# SMD_Hardware_V0_1.net
KiCad netlist of a schematic drawn in EAGLE
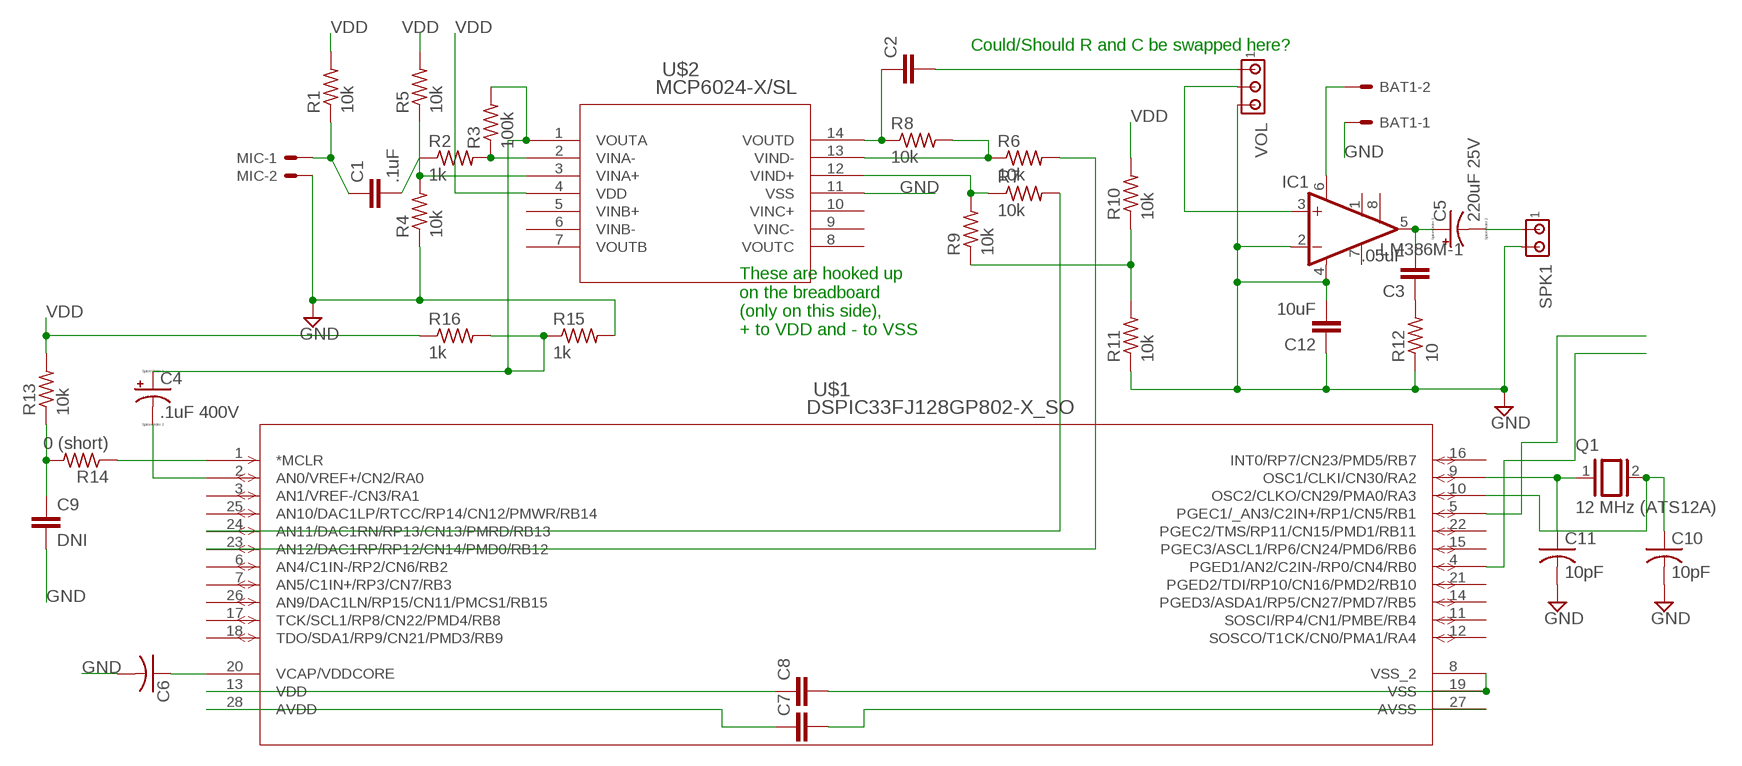
[diagram p0: schematic, sheet 1]

(export (version "E")
  (design (tool "Eeschema 10.0.6"))
  (components
    (comp (ref "BAT1")
      (value "22-23-2021")
      (footprint "eagle-import:22-23-2021")
      (fields (field (name "MF") "MOLEX"))
      (libsource (lib "eagle-import") (part "22-23-2021"))
    )
    (comp (ref "C1")
      (value ".1uF")
      (footprint "eagle-import:C0603")
      (libsource (lib "eagle-import") (part "C-EUC0603"))
    )
    (comp (ref "C2")
      (value "C-EUC0603")
      (footprint "eagle-import:C0603")
      (libsource (lib "eagle-import") (part "C-EUC0603"))
    )
    (comp (ref "C3")
      (value ".05uF")
      (footprint "eagle-import:C0603")
      (libsource (lib "eagle-import") (part "C-EUC0603"))
    )
    (comp (ref "C4")
      (value ".1uF 400V")
      (footprint "eagle-import:140CLH-0810")
      (libsource (lib "eagle-import") (part "CPOL-US140CLH-0810"))
    )
    (comp (ref "C5")
      (value "220uF 25V")
      (footprint "eagle-import:140CLH-0810")
      (libsource (lib "eagle-import") (part "CPOL-US140CLH-0810"))
    )
    (comp (ref "C6")
      (value "C-USC0805")
      (footprint "eagle-import:C0805")
      (libsource (lib "eagle-import") (part "C-USC0805"))
    )
    (comp (ref "C7")
      (value "C-EUC0805")
      (footprint "eagle-import:C0805")
      (libsource (lib "eagle-import") (part "C-EUC0805"))
    )
    (comp (ref "C8")
      (value "C-EUC0805")
      (footprint "eagle-import:C0805")
      (libsource (lib "eagle-import") (part "C-EUC0805"))
    )
    (comp (ref "C9")
      (value "DNI")
      (footprint "eagle-import:C0805")
      (libsource (lib "eagle-import") (part "C-EUC0805"))
    )
    (comp (ref "C10")
      (value "10pF")
      (footprint "eagle-import:C025-024X044")
      (libsource (lib "eagle-import") (part "C-US025-024X044"))
    )
    (comp (ref "C11")
      (value "10pF")
      (footprint "eagle-import:C025-024X044")
      (libsource (lib "eagle-import") (part "C-US025-024X044"))
    )
    (comp (ref "C12")
      (value "10uF")
      (footprint "eagle-import:C0603")
      (libsource (lib "eagle-import") (part "C-EUC0603"))
    )
    (comp (ref "IC1")
      (value "LM386M-1")
      (footprint "eagle-import:SO08")
      (libsource (lib "eagle-import") (part "LM386?-M1"))
    )
    (comp (ref "MIC")
      (value "22-23-2021")
      (footprint "eagle-import:22-23-2021")
      (fields (field (name "MF") "MOLEX"))
      (libsource (lib "eagle-import") (part "22-23-2021"))
    )
    (comp (ref "Q1")
      (value "12 MHz (ATS12A)")
      (footprint "eagle-import:Q")
      (libsource (lib "eagle-import") (part "XTAL"))
    )
    (comp (ref "R1")
      (value "10k")
      (footprint "eagle-import:R0603")
      (libsource (lib "eagle-import") (part "R-US_R0603"))
    )
    (comp (ref "R2")
      (value "1k")
      (footprint "eagle-import:R0603")
      (libsource (lib "eagle-import") (part "R-US_R0603"))
    )
    (comp (ref "R3")
      (value "100k")
      (footprint "eagle-import:R0603")
      (libsource (lib "eagle-import") (part "R-US_R0603"))
    )
    (comp (ref "R4")
      (value "10k")
      (footprint "eagle-import:R0603")
      (libsource (lib "eagle-import") (part "R-US_R0603"))
    )
    (comp (ref "R5")
      (value "10k")
      (footprint "eagle-import:R0603")
      (libsource (lib "eagle-import") (part "R-US_R0603"))
    )
    (comp (ref "R6")
      (value "10k")
      (footprint "eagle-import:R0603")
      (libsource (lib "eagle-import") (part "R-US_R0603"))
    )
    (comp (ref "R7")
      (value "10k")
      (footprint "eagle-import:R0603")
      (libsource (lib "eagle-import") (part "R-US_R0603"))
    )
    (comp (ref "R8")
      (value "10k")
      (footprint "eagle-import:R0603")
      (libsource (lib "eagle-import") (part "R-US_R0603"))
    )
    (comp (ref "R9")
      (value "10k")
      (footprint "eagle-import:R0603")
      (libsource (lib "eagle-import") (part "R-US_R0603"))
    )
    (comp (ref "R10")
      (value "10k")
      (footprint "eagle-import:R0603")
      (libsource (lib "eagle-import") (part "R-US_R0603"))
    )
    (comp (ref "R11")
      (value "10k")
      (footprint "eagle-import:R0603")
      (libsource (lib "eagle-import") (part "R-US_R0603"))
    )
    (comp (ref "R12")
      (value "10")
      (footprint "eagle-import:R0603")
      (libsource (lib "eagle-import") (part "R-US_R0603"))
    )
    (comp (ref "R13")
      (value "10k")
      (footprint "eagle-import:R0603")
      (libsource (lib "eagle-import") (part "R-US_R0603"))
    )
    (comp (ref "R14")
      (value "0 (short)")
      (footprint "eagle-import:R0603")
      (libsource (lib "eagle-import") (part "R-US_R0603"))
    )
    (comp (ref "R15")
      (value "1k")
      (footprint "eagle-import:R0603")
      (libsource (lib "eagle-import") (part "R-US_R0603"))
    )
    (comp (ref "R16")
      (value "1k")
      (footprint "eagle-import:R0603")
      (libsource (lib "eagle-import") (part "R-US_R0603"))
    )
    (comp (ref "SPK1")
      (value "MTA02-100")
      (footprint "eagle-import:10X02MTA")
      (libsource (lib "eagle-import") (part "MTA02-100"))
    )
    (comp (ref "U$1")
      (value "DSPIC33FJ128GP802-X_SO")
      (footprint "eagle-import:SOIC28-W_MC")
      (libsource (lib "eagle-import") (part "DSPIC33FJ128GP802-X_SO"))
    )
    (comp (ref "U$2")
      (value "MCP6024-X/SL")
      (footprint "eagle-import:SOIC14-N_MC")
      (libsource (lib "eagle-import") (part "MCP6024-X/SL"))
    )
    (comp (ref "VOL")
      (value "MTA03-100")
      (footprint "eagle-import:10X03MTA")
      (libsource (lib "eagle-import") (part "MTA03-100"))
    )
  )
  (nets
    (net (code "1") (name "/VDD") (class "Default")
      (node (ref "R1") (pin "2") (pinfunction "2_2") (pintype "passive"))
      (node (ref "R10") (pin "2") (pinfunction "2_2") (pintype "passive"))
      (node (ref "R13") (pin "2") (pinfunction "2_2") (pintype "passive"))
      (node (ref "R16") (pin "1") (pinfunction "1_1") (pintype "passive"))
      (node (ref "R5") (pin "2") (pinfunction "2_2") (pintype "passive"))
      (node (ref "U$2") (pin "4") (pinfunction "VDD_4") (pintype "passive"))
    )
    (net (code "2") (name "GND") (class "Default")
      (node (ref "BAT1") (pin "1") (pinfunction "S_1") (pintype "passive"))
      (node (ref "C10") (pin "2") (pinfunction "2_2") (pintype "passive"))
      (node (ref "C11") (pin "2") (pinfunction "2_2") (pintype "passive"))
      (node (ref "C12") (pin "1") (pinfunction "1_1") (pintype "passive"))
      (node (ref "C12") (pin "2") (pinfunction "2_2") (pintype "passive"))
      (node (ref "C6") (pin "2") (pinfunction "2_2") (pintype "passive"))
      (node (ref "C9") (pin "2") (pinfunction "2_2") (pintype "passive"))
      (node (ref "IC1") (pin "2") (pinfunction "-IN_2") (pintype "input"))
      (node (ref "IC1") (pin "4") (pinfunction "GND_4") (pintype "power_in"))
      (node (ref "MIC") (pin "2") (pinfunction "S_2") (pintype "passive"))
      (node (ref "R11") (pin "1") (pinfunction "1_1") (pintype "passive"))
      (node (ref "R12") (pin "1") (pinfunction "1_1") (pintype "passive"))
      (node (ref "R15") (pin "2") (pinfunction "2_2") (pintype "passive"))
      (node (ref "R4") (pin "1") (pinfunction "1_1") (pintype "passive"))
      (node (ref "SPK1") (pin "2") (pinfunction "2_2") (pintype "passive"))
      (node (ref "U$2") (pin "11") (pinfunction "VSS_11") (pintype "passive"))
      (node (ref "VOL") (pin "3") (pinfunction "3_3") (pintype "passive"))
    )
    (net (code "3") (name "Net-(BAT1B-S)") (class "Default")
      (node (ref "BAT1") (pin "2") (pinfunction "S_2") (pintype "passive"))
      (node (ref "IC1") (pin "6") (pinfunction "VS_6") (pintype "power_in"))
    )
    (net (code "4") (name "Net-(C1-Pad2)") (class "Default")
      (node (ref "C1") (pin "2") (pinfunction "2_2") (pintype "passive"))
      (node (ref "R2") (pin "1") (pinfunction "1_1") (pintype "passive"))
    )
    (net (code "5") (name "Net-(C2-Pad2)") (class "Default")
      (node (ref "C2") (pin "2") (pinfunction "2_2") (pintype "passive"))
      (node (ref "VOL") (pin "1") (pinfunction "1_1") (pintype "passive"))
    )
    (net (code "6") (name "Net-(C3-Pad1)") (class "Default")
      (node (ref "C3") (pin "1") (pinfunction "1_1") (pintype "passive"))
      (node (ref "R12") (pin "2") (pinfunction "2_2") (pintype "passive"))
    )
    (net (code "7") (name "Net-(C5-Pad-)") (class "Default")
      (node (ref "C5") (pin "-") (pinfunction "-_-") (pintype "passive"))
      (node (ref "SPK1") (pin "1") (pinfunction "1_1") (pintype "passive"))
    )
    (net (code "8") (name "Net-(C9-Pad1)") (class "Default")
      (node (ref "C9") (pin "1") (pinfunction "1_1") (pintype "passive"))
      (node (ref "R13") (pin "1") (pinfunction "1_1") (pintype "passive"))
      (node (ref "R14") (pin "2") (pinfunction "2_2") (pintype "passive"))
    )
    (net (code "9") (name "Net-(IC1-+IN)") (class "Default")
      (node (ref "IC1") (pin "3") (pinfunction "+IN_3") (pintype "input"))
      (node (ref "VOL") (pin "2") (pinfunction "2_2") (pintype "passive"))
    )
    (net (code "10") (name "Net-(IC1-OUT)") (class "Default")
      (node (ref "C3") (pin "2") (pinfunction "2_2") (pintype "passive"))
      (node (ref "C5") (pin "+") (pinfunction "+_+") (pintype "passive"))
      (node (ref "IC1") (pin "5") (pinfunction "OUT_5") (pintype "output"))
    )
    (net (code "11") (name "Net-(MICA-S)") (class "Default")
      (node (ref "C1") (pin "1") (pinfunction "1_1") (pintype "passive"))
      (node (ref "MIC") (pin "1") (pinfunction "S_1") (pintype "passive"))
      (node (ref "R1") (pin "1") (pinfunction "1_1") (pintype "passive"))
    )
    (net (code "12") (name "Net-(R10-Pad1)") (class "Default")
      (node (ref "R10") (pin "1") (pinfunction "1_1") (pintype "passive"))
      (node (ref "R11") (pin "2") (pinfunction "2_2") (pintype "passive"))
      (node (ref "R9") (pin "1") (pinfunction "1_1") (pintype "passive"))
    )
    (net (code "13") (name "Net-(U$1-*MCLR)") (class "Default")
      (node (ref "R14") (pin "1") (pinfunction "1_1") (pintype "passive"))
      (node (ref "U$1") (pin "1") (pinfunction "*MCLR_1") (pintype "input"))
    )
    (net (code "14") (name "Net-(U$1-AN0{slash}VREF+{slash}CN2{slash}RA0)") (class "Default")
      (node (ref "C4") (pin "-") (pinfunction "-_-") (pintype "passive"))
      (node (ref "U$1") (pin "2") (pinfunction "AN0/VREF+/CN2/RA0_2") (pintype "bidirectional"))
    )
    (net (code "15") (name "Net-(U$1-AN11{slash}DAC1RN{slash}RP13{slash}CN13{slash}PMRD{slash}RB13)") (class "Default")
      (node (ref "R7") (pin "2") (pinfunction "2_2") (pintype "passive"))
      (node (ref "U$1") (pin "24") (pinfunction "AN11/DAC1RN/RP13/CN13/PMRD/RB13_24") (pintype "bidirectional"))
    )
    (net (code "16") (name "Net-(U$1-AN12{slash}DAC1RP{slash}RP12{slash}CN14{slash}PMD0{slash}RB12)") (class "Default")
      (node (ref "R6") (pin "2") (pinfunction "2_2") (pintype "passive"))
      (node (ref "U$1") (pin "23") (pinfunction "AN12/DAC1RP/RP12/CN14/PMD0/RB12_23") (pintype "bidirectional"))
    )
    (net (code "17") (name "Net-(U$1-AVDD)") (class "Default")
      (node (ref "C7") (pin "1") (pinfunction "1_1") (pintype "passive"))
      (node (ref "U$1") (pin "28") (pinfunction "AVDD_28") (pintype "power_in"))
    )
    (net (code "18") (name "Net-(U$1-AVSS)") (class "Default")
      (node (ref "C7") (pin "2") (pinfunction "2_2") (pintype "passive"))
      (node (ref "U$1") (pin "27") (pinfunction "AVSS_27") (pintype "power_in"))
    )
    (net (code "19") (name "Net-(U$1-OSC1{slash}CLKI{slash}CN30{slash}RA2)") (class "Default")
      (node (ref "C11") (pin "1") (pinfunction "1_1") (pintype "passive"))
      (node (ref "Q1") (pin "1") (pinfunction "1_1") (pintype "passive"))
      (node (ref "U$1") (pin "9") (pinfunction "OSC1/CLKI/CN30/RA2_9") (pintype "bidirectional"))
    )
    (net (code "20") (name "Net-(U$1-OSC2{slash}CLKO{slash}CN29{slash}PMA0{slash}RA3)") (class "Default")
      (node (ref "C10") (pin "1") (pinfunction "1_1") (pintype "passive"))
      (node (ref "Q1") (pin "2") (pinfunction "2_2") (pintype "passive"))
      (node (ref "U$1") (pin "10") (pinfunction "OSC2/CLKO/CN29/PMA0/RA3_10") (pintype "bidirectional"))
    )
    (net (code "21") (name "Net-(U$1-VCAP{slash}VDDCORE)") (class "Default")
      (node (ref "C6") (pin "1") (pinfunction "1_1") (pintype "passive"))
      (node (ref "U$1") (pin "20") (pinfunction "VCAP/VDDCORE_20") (pintype "power_in"))
    )
    (net (code "22") (name "Net-(U$1-VDD)") (class "Default")
      (node (ref "C8") (pin "1") (pinfunction "1_1") (pintype "passive"))
      (node (ref "U$1") (pin "13") (pinfunction "VDD_13") (pintype "power_in"))
    )
    (net (code "23") (name "Net-(U$1-VSS)") (class "Default")
      (node (ref "C8") (pin "2") (pinfunction "2_2") (pintype "passive"))
      (node (ref "U$1") (pin "19") (pinfunction "VSS_19") (pintype "power_in"))
      (node (ref "U$1") (pin "8") (pinfunction "VSS_2_8") (pintype "power_in"))
    )
    (net (code "24") (name "Net-(U$2-VINA+)") (class "Default")
      (node (ref "R4") (pin "2") (pinfunction "2_2") (pintype "passive"))
      (node (ref "R5") (pin "1") (pinfunction "1_1") (pintype "passive"))
      (node (ref "U$2") (pin "3") (pinfunction "VINA+_3") (pintype "passive"))
    )
    (net (code "25") (name "Net-(U$2-VINA-)") (class "Default")
      (node (ref "R2") (pin "2") (pinfunction "2_2") (pintype "passive"))
      (node (ref "R3") (pin "1") (pinfunction "1_1") (pintype "passive"))
      (node (ref "U$2") (pin "2") (pinfunction "VINA-_2") (pintype "passive"))
    )
    (net (code "26") (name "Net-(U$2-VIND+)") (class "Default")
      (node (ref "R7") (pin "1") (pinfunction "1_1") (pintype "passive"))
      (node (ref "R9") (pin "2") (pinfunction "2_2") (pintype "passive"))
      (node (ref "U$2") (pin "12") (pinfunction "VIND+_12") (pintype "passive"))
    )
    (net (code "27") (name "Net-(U$2-VIND-)") (class "Default")
      (node (ref "R6") (pin "1") (pinfunction "1_1") (pintype "passive"))
      (node (ref "R8") (pin "2") (pinfunction "2_2") (pintype "passive"))
      (node (ref "U$2") (pin "13") (pinfunction "VIND-_13") (pintype "passive"))
    )
    (net (code "28") (name "Net-(U$2-VOUTA)") (class "Default")
      (node (ref "C4") (pin "+") (pinfunction "+_+") (pintype "passive"))
      (node (ref "R15") (pin "1") (pinfunction "1_1") (pintype "passive"))
      (node (ref "R16") (pin "2") (pinfunction "2_2") (pintype "passive"))
      (node (ref "R3") (pin "2") (pinfunction "2_2") (pintype "passive"))
      (node (ref "U$2") (pin "1") (pinfunction "VOUTA_1") (pintype "passive"))
    )
    (net (code "29") (name "Net-(U$2-VOUTD)") (class "Default")
      (node (ref "C2") (pin "1") (pinfunction "1_1") (pintype "passive"))
      (node (ref "R8") (pin "1") (pinfunction "1_1") (pintype "passive"))
      (node (ref "U$2") (pin "14") (pinfunction "VOUTD_14") (pintype "passive"))
    )
    (net (code "30") (name "unconnected-(IC1-BYPASS-Pad7)") (class "Default")
      (node (ref "IC1") (pin "7") (pinfunction "BYPASS_7") (pintype "passive"))
    )
    (net (code "31") (name "unconnected-(IC1-GAIN-Pad1)") (class "Default")
      (node (ref "IC1") (pin "1") (pinfunction "GAIN_1") (pintype "passive"))
    )
    (net (code "32") (name "unconnected-(IC1-GAIN-Pad8)") (class "Default")
      (node (ref "IC1") (pin "8") (pinfunction "GAIN_8") (pintype "passive"))
    )
    (net (code "33") (name "unconnected-(U$1-AN1{slash}VREF-{slash}CN3{slash}RA1-Pad3)") (class "Default")
      (node (ref "U$1") (pin "3") (pinfunction "AN1/VREF-/CN3/RA1_3") (pintype "bidirectional"))
    )
    (net (code "34") (name "unconnected-(U$1-AN4{slash}C1IN-{slash}RP2{slash}CN6{slash}RB2-Pad6)") (class "Default")
      (node (ref "U$1") (pin "6") (pinfunction "AN4/C1IN-/RP2/CN6/RB2_6") (pintype "bidirectional"))
    )
    (net (code "35") (name "unconnected-(U$1-AN5{slash}C1IN+{slash}RP3{slash}CN7{slash}RB3-Pad7)") (class "Default")
      (node (ref "U$1") (pin "7") (pinfunction "AN5/C1IN+/RP3/CN7/RB3_7") (pintype "bidirectional"))
    )
    (net (code "36") (name "unconnected-(U$1-AN9{slash}DAC1LN{slash}RP15{slash}CN11{slash}PMCS1{slash}RB15-Pad26)") (class "Default")
      (node (ref "U$1") (pin "26") (pinfunction "AN9/DAC1LN/RP15/CN11/PMCS1/RB15_26") (pintype "bidirectional"))
    )
    (net (code "37") (name "unconnected-(U$1-AN10{slash}DAC1LP{slash}RTCC{slash}RP14{slash}CN12{slash}PMWR{slash}RB14-Pad25)") (class "Default")
      (node (ref "U$1") (pin "25") (pinfunction "AN10/DAC1LP/RTCC/RP14/CN12/PMWR/RB14_25") (pintype "bidirectional"))
    )
    (net (code "38") (name "unconnected-(U$1-INT0{slash}RP7{slash}CN23{slash}PMD5{slash}RB7-Pad16)") (class "Default")
      (node (ref "U$1") (pin "16") (pinfunction "INT0/RP7/CN23/PMD5/RB7_16") (pintype "bidirectional"))
    )
    (net (code "39") (name "unconnected-(U$1-PGEC1{slash}_AN3{slash}C2IN+{slash}RP1{slash}CN5{slash}RB1-Pad5)") (class "Default")
      (node (ref "U$1") (pin "5") (pinfunction "PGEC1/_AN3/C2IN+/RP1/CN5/RB1_5") (pintype "bidirectional"))
    )
    (net (code "40") (name "unconnected-(U$1-PGEC2{slash}TMS{slash}RP11{slash}CN15{slash}PMD1{slash}RB11-Pad22)") (class "Default")
      (node (ref "U$1") (pin "22") (pinfunction "PGEC2/TMS/RP11/CN15/PMD1/RB11_22") (pintype "bidirectional"))
    )
    (net (code "41") (name "unconnected-(U$1-PGEC3{slash}ASCL1{slash}RP6{slash}CN24{slash}PMD6{slash}RB6-Pad15)") (class "Default")
      (node (ref "U$1") (pin "15") (pinfunction "PGEC3/ASCL1/RP6/CN24/PMD6/RB6_15") (pintype "bidirectional"))
    )
    (net (code "42") (name "unconnected-(U$1-PGED1{slash}AN2{slash}C2IN-{slash}RP0{slash}CN4{slash}RB0-Pad4)") (class "Default")
      (node (ref "U$1") (pin "4") (pinfunction "PGED1/AN2/C2IN-/RP0/CN4/RB0_4") (pintype "bidirectional"))
    )
    (net (code "43") (name "unconnected-(U$1-PGED2{slash}TDI{slash}RP10{slash}CN16{slash}PMD2{slash}RB10-Pad21)") (class "Default")
      (node (ref "U$1") (pin "21") (pinfunction "PGED2/TDI/RP10/CN16/PMD2/RB10_21") (pintype "bidirectional"))
    )
    (net (code "44") (name "unconnected-(U$1-PGED3{slash}ASDA1{slash}RP5{slash}CN27{slash}PMD7{slash}RB5-Pad14)") (class "Default")
      (node (ref "U$1") (pin "14") (pinfunction "PGED3/ASDA1/RP5/CN27/PMD7/RB5_14") (pintype "bidirectional"))
    )
    (net (code "45") (name "unconnected-(U$1-SOSCI{slash}RP4{slash}CN1{slash}PMBE{slash}RB4-Pad11)") (class "Default")
      (node (ref "U$1") (pin "11") (pinfunction "SOSCI/RP4/CN1/PMBE/RB4_11") (pintype "bidirectional"))
    )
    (net (code "46") (name "unconnected-(U$1-SOSCO{slash}T1CK{slash}CN0{slash}PMA1{slash}RA4-Pad12)") (class "Default")
      (node (ref "U$1") (pin "12") (pinfunction "SOSCO/T1CK/CN0/PMA1/RA4_12") (pintype "bidirectional"))
    )
    (net (code "47") (name "unconnected-(U$1-TCK{slash}SCL1{slash}RP8{slash}CN22{slash}PMD4{slash}RB8-Pad17)") (class "Default")
      (node (ref "U$1") (pin "17") (pinfunction "TCK/SCL1/RP8/CN22/PMD4/RB8_17") (pintype "bidirectional"))
    )
    (net (code "48") (name "unconnected-(U$1-TDO{slash}SDA1{slash}RP9{slash}CN21{slash}PMD3{slash}RB9-Pad18)") (class "Default")
      (node (ref "U$1") (pin "18") (pinfunction "TDO/SDA1/RP9/CN21/PMD3/RB9_18") (pintype "bidirectional"))
    )
    (net (code "49") (name "unconnected-(U$2-VINB+-Pad5)") (class "Default")
      (node (ref "U$2") (pin "5") (pinfunction "VINB+_5") (pintype "passive"))
    )
    (net (code "50") (name "unconnected-(U$2-VINB--Pad6)") (class "Default")
      (node (ref "U$2") (pin "6") (pinfunction "VINB-_6") (pintype "passive"))
    )
    (net (code "51") (name "unconnected-(U$2-VINC+-Pad10)") (class "Default")
      (node (ref "U$2") (pin "10") (pinfunction "VINC+_10") (pintype "passive"))
    )
    (net (code "52") (name "unconnected-(U$2-VINC--Pad9)") (class "Default")
      (node (ref "U$2") (pin "9") (pinfunction "VINC-_9") (pintype "passive"))
    )
    (net (code "53") (name "unconnected-(U$2-VOUTB-Pad7)") (class "Default")
      (node (ref "U$2") (pin "7") (pinfunction "VOUTB_7") (pintype "passive"))
    )
    (net (code "54") (name "unconnected-(U$2-VOUTC-Pad8)") (class "Default")
      (node (ref "U$2") (pin "8") (pinfunction "VOUTC_8") (pintype "passive"))
    )
  )
)
